# tractor_2v1.net
KiCad netlist of a schematic drawn in EAGLE
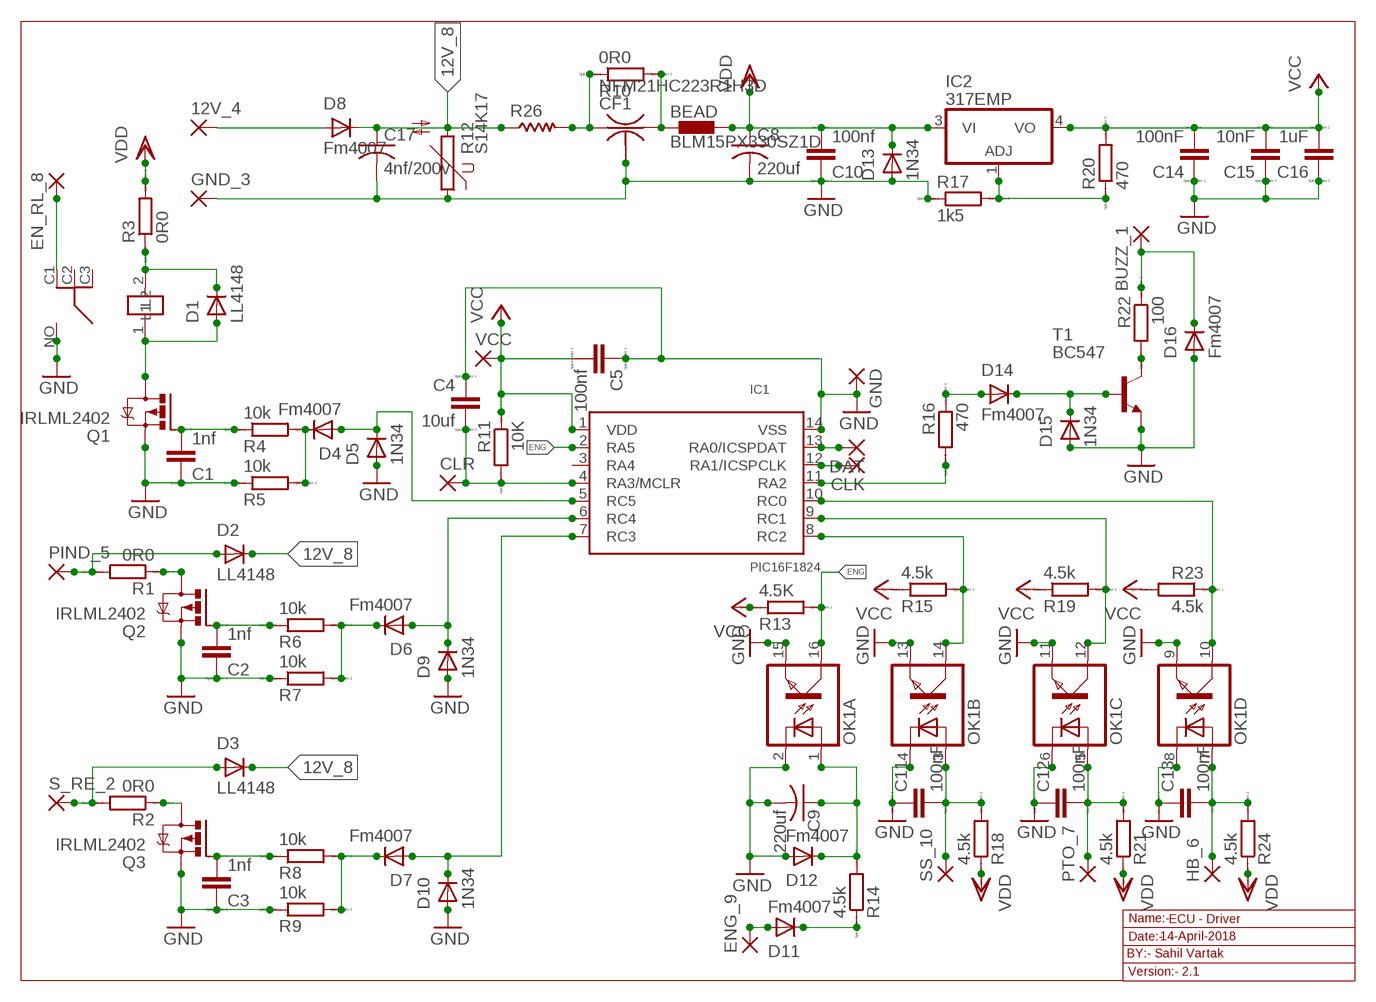
[diagram p0: schematic, sheet 1]

(export (version "E")
  (design (tool "Eeschema 10.0.6"))
  (components
    (comp (ref "12V_4")
      (value "2,54/1,1")
      (footprint "eagle-import:2,54_1,1")
      (libsource (lib "eagle-import") (part "2,54/1,1"))
    )
    (comp (ref "BEAD")
      (value "BLM15PX330SZ1D")
      (footprint "eagle-import:0402")
      (libsource (lib "eagle-import") (part "BLM15HG601SN1"))
    )
    (comp (ref "BUZZ_1")
      (value "2,54/1,1")
      (footprint "eagle-import:2,54_1,1")
      (libsource (lib "eagle-import") (part "2,54/1,1"))
    )
    (comp (ref "C1")
      (value "1nf")
      (footprint "eagle-import:C0603")
      (libsource (lib "eagle-import") (part "CC0603"))
    )
    (comp (ref "C2")
      (value "1nf")
      (footprint "eagle-import:C0603")
      (libsource (lib "eagle-import") (part "CC0603"))
    )
    (comp (ref "C3")
      (value "1nf")
      (footprint "eagle-import:C0603")
      (libsource (lib "eagle-import") (part "CC0603"))
    )
    (comp (ref "C4")
      (value "10uf")
      (footprint "eagle-import:C0603")
      (libsource (lib "eagle-import") (part "CC0603"))
    )
    (comp (ref "C5")
      (value "100nf")
      (footprint "eagle-import:C0603")
      (libsource (lib "eagle-import") (part "CC0603"))
    )
    (comp (ref "C8")
      (value "220uf")
      (footprint "eagle-import:C025-025X050")
      (libsource (lib "eagle-import") (part "C-US025-025X050"))
    )
    (comp (ref "C9")
      (value "220uf")
      (footprint "eagle-import:C025-025X050")
      (libsource (lib "eagle-import") (part "C-US025-025X050"))
    )
    (comp (ref "C10")
      (value "100nf")
      (footprint "eagle-import:C0603")
      (libsource (lib "eagle-import") (part "CC0603"))
    )
    (comp (ref "C11")
      (value "100nF")
      (footprint "eagle-import:C0603")
      (libsource (lib "eagle-import") (part "CC0603"))
    )
    (comp (ref "C12")
      (value "100nF")
      (footprint "eagle-import:C0603")
      (libsource (lib "eagle-import") (part "CC0603"))
    )
    (comp (ref "C13")
      (value "100nF")
      (footprint "eagle-import:C0603")
      (libsource (lib "eagle-import") (part "CC0603"))
    )
    (comp (ref "C14")
      (value "100nF")
      (footprint "eagle-import:C0603")
      (libsource (lib "eagle-import") (part "CC0603"))
    )
    (comp (ref "C15")
      (value "10nF")
      (footprint "eagle-import:C0603")
      (libsource (lib "eagle-import") (part "CC0603"))
    )
    (comp (ref "C16")
      (value "1uF")
      (footprint "eagle-import:C0603")
      (libsource (lib "eagle-import") (part "CC0603"))
    )
    (comp (ref "C17")
      (value "4nf/200v")
      (footprint "eagle-import:C050-045X075")
      (libsource (lib "eagle-import") (part "C-US050-045X075"))
    )
    (comp (ref "CF1")
      (value "NFM21HC223R1H3D")
      (footprint "eagle-import:NFM3DC")
      (fields (field (name "MF") "FARNELL") (field (name "MPN") "NFM3DCC470U1H3L"))
      (libsource (lib "eagle-import") (part "NFM3DC"))
    )
    (comp (ref "CLK")
      (value "1,6/0,8")
      (footprint "eagle-import:1,6_0,8")
      (libsource (lib "eagle-import") (part "1,6/0,8"))
    )
    (comp (ref "CLR")
      (value "1,6/0,8")
      (footprint "eagle-import:1,6_0,8")
      (libsource (lib "eagle-import") (part "1,6/0,8"))
    )
    (comp (ref "D1")
      (value "LL4148")
      (footprint "eagle-import:SMA-DO214AC")
      (libsource (lib "eagle-import") (part "GF1"))
    )
    (comp (ref "D2")
      (value "LL4148")
      (footprint "eagle-import:SMA-DO214AC")
      (libsource (lib "eagle-import") (part "GF1"))
    )
    (comp (ref "D3")
      (value "LL4148")
      (footprint "eagle-import:SMA-DO214AC")
      (libsource (lib "eagle-import") (part "GF1"))
    )
    (comp (ref "D4")
      (value "Fm4007")
      (footprint "eagle-import:SMA-DO214AC")
      (libsource (lib "eagle-import") (part "GF1"))
    )
    (comp (ref "D5")
      (value "1N34")
      (footprint "eagle-import:SMA-DO214AC")
      (libsource (lib "eagle-import") (part "GF1"))
    )
    (comp (ref "D6")
      (value "Fm4007")
      (footprint "eagle-import:SMA-DO214AC")
      (libsource (lib "eagle-import") (part "GF1"))
    )
    (comp (ref "D7")
      (value "Fm4007")
      (footprint "eagle-import:SMA-DO214AC")
      (libsource (lib "eagle-import") (part "GF1"))
    )
    (comp (ref "D8")
      (value "Fm4007")
      (footprint "eagle-import:SMA-DO214AC")
      (libsource (lib "eagle-import") (part "GF1"))
    )
    (comp (ref "D9")
      (value "1N34")
      (footprint "eagle-import:SMA-DO214AC")
      (libsource (lib "eagle-import") (part "GF1"))
    )
    (comp (ref "D10")
      (value "1N34")
      (footprint "eagle-import:SMA-DO214AC")
      (libsource (lib "eagle-import") (part "GF1"))
    )
    (comp (ref "D11")
      (value "Fm4007")
      (footprint "eagle-import:SMA-DO214AC")
      (libsource (lib "eagle-import") (part "GF1"))
    )
    (comp (ref "D12")
      (value "Fm4007")
      (footprint "eagle-import:SMA-DO214AC")
      (libsource (lib "eagle-import") (part "GF1"))
    )
    (comp (ref "D13")
      (value "1N34")
      (footprint "eagle-import:SMA-DO214AC")
      (libsource (lib "eagle-import") (part "GF1"))
    )
    (comp (ref "D14")
      (value "Fm4007")
      (footprint "eagle-import:SMA-DO214AC")
      (libsource (lib "eagle-import") (part "GF1"))
    )
    (comp (ref "D15")
      (value "1N34")
      (footprint "eagle-import:SMA-DO214AC")
      (libsource (lib "eagle-import") (part "GF1"))
    )
    (comp (ref "D16")
      (value "Fm4007")
      (footprint "eagle-import:SMA-DO214AC")
      (libsource (lib "eagle-import") (part "GF1"))
    )
    (comp (ref "DAT")
      (value "1,6/0,8")
      (footprint "eagle-import:1,6_0,8")
      (libsource (lib "eagle-import") (part "1,6/0,8"))
    )
    (comp (ref "ENG_9")
      (value "2,54/1,1")
      (footprint "eagle-import:2,54_1,1")
      (libsource (lib "eagle-import") (part "2,54/1,1"))
    )
    (comp (ref "EN_RL_8")
      (value "2,54/1,1")
      (footprint "eagle-import:2,54_1,1")
      (libsource (lib "eagle-import") (part "2,54/1,1"))
    )
    (comp (ref "GND")
      (value "1,6/0,8")
      (footprint "eagle-import:1,6_0,8")
      (libsource (lib "eagle-import") (part "1,6/0,8"))
    )
    (comp (ref "GND_3")
      (value "2,54/1,1")
      (footprint "eagle-import:2,54_1,1")
      (libsource (lib "eagle-import") (part "2,54/1,1"))
    )
    (comp (ref "HB_6")
      (value "2,54/1,1")
      (footprint "eagle-import:2,54_1,1")
      (libsource (lib "eagle-import") (part "2,54/1,1"))
    )
    (comp (ref "IC1")
      (value "PIC16F1824")
      (footprint "eagle-import:SO-14")
      (libsource (lib "eagle-import") (part "PIC16F1824"))
    )
    (comp (ref "IC2")
      (value "317EMP")
      (footprint "eagle-import:SOT223")
      (libsource (lib "eagle-import") (part "317EMP"))
    )
    (comp (ref "K1")
      (value "RL703")
      (footprint "eagle-import:RL703")
      (libsource (lib "eagle-import") (part "RL703"))
    )
    (comp (ref "OK1")
      (value "TLP283-4")
      (footprint "eagle-import:MINI-FLAT-16")
      (libsource (lib "eagle-import") (part "TLP283-4"))
    )
    (comp (ref "PIND_5")
      (value "2,54/1,1")
      (footprint "eagle-import:2,54_1,1")
      (libsource (lib "eagle-import") (part "2,54/1,1"))
    )
    (comp (ref "PTO_7")
      (value "2,54/1,1")
      (footprint "eagle-import:2,54_1,1")
      (libsource (lib "eagle-import") (part "2,54/1,1"))
    )
    (comp (ref "Q1")
      (value "IRLML2402")
      (footprint "eagle-import:MICRO3")
      (libsource (lib "eagle-import") (part "IRLML5203"))
    )
    (comp (ref "Q2")
      (value "IRLML2402")
      (footprint "eagle-import:MICRO3")
      (libsource (lib "eagle-import") (part "IRLML5203"))
    )
    (comp (ref "Q3")
      (value "IRLML2402")
      (footprint "eagle-import:MICRO3")
      (libsource (lib "eagle-import") (part "IRLML5203"))
    )
    (comp (ref "R1")
      (value "0R0")
      (footprint "eagle-import:R0603")
      (libsource (lib "eagle-import") (part "RR0603"))
    )
    (comp (ref "R2")
      (value "0R0")
      (footprint "eagle-import:R0603")
      (libsource (lib "eagle-import") (part "RR0603"))
    )
    (comp (ref "R3")
      (value "0R0")
      (footprint "eagle-import:R0603")
      (libsource (lib "eagle-import") (part "RR0603"))
    )
    (comp (ref "R4")
      (value "10k")
      (footprint "eagle-import:R0603")
      (libsource (lib "eagle-import") (part "RR0603"))
    )
    (comp (ref "R5")
      (value "10k")
      (footprint "eagle-import:R0603")
      (libsource (lib "eagle-import") (part "RR0603"))
    )
    (comp (ref "R6")
      (value "10k")
      (footprint "eagle-import:R0603")
      (libsource (lib "eagle-import") (part "RR0603"))
    )
    (comp (ref "R7")
      (value "10k")
      (footprint "eagle-import:R0603")
      (libsource (lib "eagle-import") (part "RR0603"))
    )
    (comp (ref "R8")
      (value "10k")
      (footprint "eagle-import:R0603")
      (libsource (lib "eagle-import") (part "RR0603"))
    )
    (comp (ref "R9")
      (value "10k")
      (footprint "eagle-import:R0603")
      (libsource (lib "eagle-import") (part "RR0603"))
    )
    (comp (ref "R10")
      (value "0R0")
      (footprint "eagle-import:R0603")
      (libsource (lib "eagle-import") (part "RR0603"))
    )
    (comp (ref "R11")
      (value "10K")
      (footprint "eagle-import:R0603")
      (libsource (lib "eagle-import") (part "RR0603"))
    )
    (comp (ref "R12")
      (value "S14K17")
      (footprint "eagle-import:S14K17")
      (libsource (lib "eagle-import") (part "S14K17"))
    )
    (comp (ref "R13")
      (value "4.5K")
      (footprint "eagle-import:R0603")
      (libsource (lib "eagle-import") (part "RR0603"))
    )
    (comp (ref "R14")
      (value "4.5k")
      (footprint "eagle-import:R0603")
      (libsource (lib "eagle-import") (part "RR0603"))
    )
    (comp (ref "R15")
      (value "4.5k")
      (footprint "eagle-import:R0603")
      (libsource (lib "eagle-import") (part "RR0603"))
    )
    (comp (ref "R16")
      (value "470")
      (footprint "eagle-import:R0603")
      (libsource (lib "eagle-import") (part "RR0603"))
    )
    (comp (ref "R17")
      (value "1k5")
      (footprint "eagle-import:R0603")
      (libsource (lib "eagle-import") (part "RR0603"))
    )
    (comp (ref "R18")
      (value "4.5k")
      (footprint "eagle-import:R0603")
      (libsource (lib "eagle-import") (part "RR0603"))
    )
    (comp (ref "R19")
      (value "4.5k")
      (footprint "eagle-import:R0603")
      (libsource (lib "eagle-import") (part "RR0603"))
    )
    (comp (ref "R20")
      (value "470")
      (footprint "eagle-import:R0603")
      (libsource (lib "eagle-import") (part "RR0603"))
    )
    (comp (ref "R21")
      (value "4.5k")
      (footprint "eagle-import:R0603")
      (libsource (lib "eagle-import") (part "RR0603"))
    )
    (comp (ref "R22")
      (value "100")
      (footprint "eagle-import:R0603")
      (libsource (lib "eagle-import") (part "RR0603"))
    )
    (comp (ref "R23")
      (value "4.5k")
      (footprint "eagle-import:R0603")
      (libsource (lib "eagle-import") (part "RR0603"))
    )
    (comp (ref "R24")
      (value "4.5k")
      (footprint "eagle-import:R0603")
      (libsource (lib "eagle-import") (part "RR0603"))
    )
    (comp (ref "R26")
      (value "R-US_WSC2515")
      (footprint "eagle-import:WSC2515")
      (libsource (lib "eagle-import") (part "R-US_WSC2515"))
    )
    (comp (ref "SS_10")
      (value "2,54/1,1")
      (footprint "eagle-import:2,54_1,1")
      (libsource (lib "eagle-import") (part "2,54/1,1"))
    )
    (comp (ref "S_RE_2")
      (value "2,54/1,1")
      (footprint "eagle-import:2,54_1,1")
      (libsource (lib "eagle-import") (part "2,54/1,1"))
    )
    (comp (ref "T1")
      (value "BC547")
      (footprint "eagle-import:TO92")
      (libsource (lib "eagle-import") (part "BC547"))
    )
    (comp (ref "VCC")
      (value "1,6/0,8")
      (footprint "eagle-import:1,6_0,8")
      (libsource (lib "eagle-import") (part "1,6/0,8"))
    )
  )
  (nets
    (net (code "1") (name "12V_8") (class "Default")
      (node (ref "C17") (pin "1") (pinfunction "1_1") (pintype "passive"))
      (node (ref "D2") (pin "K") (pinfunction "C_K") (pintype "passive"))
      (node (ref "D3") (pin "K") (pinfunction "C_K") (pintype "passive"))
      (node (ref "D8") (pin "K") (pinfunction "C_K") (pintype "passive"))
      (node (ref "R12") (pin "2") (pinfunction "2_2") (pintype "passive"))
      (node (ref "R26") (pin "1") (pinfunction "1_1") (pintype "passive"))
    )
    (net (code "2") (name "ENG") (class "Default")
      (node (ref "IC1") (pin "2") (pinfunction "RA5_2") (pintype "bidirectional"))
      (node (ref "OK1") (pin "16") (pinfunction "COL_16") (pintype "passive"))
      (node (ref "R13") (pin "2") (pinfunction "2_2") (pintype "passive"))
    )
    (net (code "3") (name "GND") (class "Default")
      (node (ref "C1") (pin "1") (pinfunction "1_1") (pintype "passive"))
      (node (ref "C10") (pin "1") (pinfunction "1_1") (pintype "passive"))
      (node (ref "C11") (pin "1") (pinfunction "1_1") (pintype "passive"))
      (node (ref "C12") (pin "1") (pinfunction "1_1") (pintype "passive"))
      (node (ref "C13") (pin "1") (pinfunction "1_1") (pintype "passive"))
      (node (ref "C14") (pin "1") (pinfunction "1_1") (pintype "passive"))
      (node (ref "C15") (pin "1") (pinfunction "1_1") (pintype "passive"))
      (node (ref "C16") (pin "1") (pinfunction "1_1") (pintype "passive"))
      (node (ref "C17") (pin "2") (pinfunction "2_2") (pintype "passive"))
      (node (ref "C2") (pin "1") (pinfunction "1_1") (pintype "passive"))
      (node (ref "C3") (pin "1") (pinfunction "1_1") (pintype "passive"))
      (node (ref "C4") (pin "1") (pinfunction "1_1") (pintype "passive"))
      (node (ref "C5") (pin "1") (pinfunction "1_1") (pintype "passive"))
      (node (ref "C8") (pin "2") (pinfunction "2_2") (pintype "passive"))
      (node (ref "C9") (pin "2") (pinfunction "2_2") (pintype "passive"))
      (node (ref "CF1") (pin "2@1") (pinfunction "2_2@1") (pintype "passive"))
      (node (ref "D10") (pin "A") (pinfunction "A_A") (pintype "passive"))
      (node (ref "D12") (pin "A") (pinfunction "A_A") (pintype "passive"))
      (node (ref "D13") (pin "A") (pinfunction "A_A") (pintype "passive"))
      (node (ref "D15") (pin "A") (pinfunction "A_A") (pintype "passive"))
      (node (ref "D16") (pin "A") (pinfunction "A_A") (pintype "passive"))
      (node (ref "D5") (pin "A") (pinfunction "A_A") (pintype "passive"))
      (node (ref "D9") (pin "A") (pinfunction "A_A") (pintype "passive"))
      (node (ref "GND") (pin "1") (pinfunction "P_1") (pintype "passive"))
      (node (ref "GND_3") (pin "1") (pinfunction "P_1") (pintype "passive"))
      (node (ref "IC1") (pin "14") (pinfunction "VSS_14") (pintype "bidirectional"))
      (node (ref "K1") (pin "NO") (pinfunction "NO_NO") (pintype "bidirectional"))
      (node (ref "OK1") (pin "11") (pinfunction "EMIT_11") (pintype "passive"))
      (node (ref "OK1") (pin "13") (pinfunction "EMIT_13") (pintype "passive"))
      (node (ref "OK1") (pin "15") (pinfunction "EMIT_15") (pintype "passive"))
      (node (ref "OK1") (pin "2") (pinfunction "C_2") (pintype "passive"))
      (node (ref "OK1") (pin "4") (pinfunction "C_4") (pintype "passive"))
      (node (ref "OK1") (pin "6") (pinfunction "C_6") (pintype "passive"))
      (node (ref "OK1") (pin "8") (pinfunction "C_8") (pintype "passive"))
      (node (ref "OK1") (pin "9") (pinfunction "EMIT_9") (pintype "passive"))
      (node (ref "Q1") (pin "2") (pinfunction "S_2") (pintype "passive"))
      (node (ref "Q2") (pin "2") (pinfunction "S_2") (pintype "passive"))
      (node (ref "Q3") (pin "2") (pinfunction "S_2") (pintype "passive"))
      (node (ref "R12") (pin "1") (pinfunction "1_1") (pintype "passive"))
      (node (ref "R17") (pin "1") (pinfunction "1_1") (pintype "passive"))
      (node (ref "R5") (pin "1") (pinfunction "1_1") (pintype "passive"))
      (node (ref "R7") (pin "1") (pinfunction "1_1") (pintype "passive"))
      (node (ref "R9") (pin "1") (pinfunction "1_1") (pintype "passive"))
      (node (ref "T1") (pin "1") (pinfunction "E_1") (pintype "passive"))
    )
    (net (code "4") (name "Net-(12V_4-P)") (class "Default")
      (node (ref "12V_4") (pin "1") (pinfunction "P_1") (pintype "passive"))
      (node (ref "D8") (pin "A") (pinfunction "A_A") (pintype "passive"))
    )
    (net (code "5") (name "Net-(BEAD-Pad1)") (class "Default")
      (node (ref "BEAD") (pin "1") (pinfunction "1_1") (pintype "passive"))
      (node (ref "CF1") (pin "3") (pinfunction "3_3") (pintype "passive"))
      (node (ref "R10") (pin "2") (pinfunction "2_2") (pintype "passive"))
    )
    (net (code "6") (name "Net-(BUZZ_1-P)") (class "Default")
      (node (ref "BUZZ_1") (pin "1") (pinfunction "P_1") (pintype "passive"))
      (node (ref "D16") (pin "K") (pinfunction "C_K") (pintype "passive"))
      (node (ref "R22") (pin "1") (pinfunction "1_1") (pintype "passive"))
    )
    (net (code "7") (name "Net-(CF1-Pad1)") (class "Default")
      (node (ref "CF1") (pin "1") (pinfunction "1_1") (pintype "passive"))
      (node (ref "R10") (pin "1") (pinfunction "1_1") (pintype "passive"))
      (node (ref "R26") (pin "2") (pinfunction "2_2") (pintype "passive"))
    )
    (net (code "8") (name "Net-(CLK-P)") (class "Default")
      (node (ref "CLK") (pin "1") (pinfunction "P_1") (pintype "passive"))
      (node (ref "IC1") (pin "12") (pinfunction "RA1/ICSPCLK_12") (pintype "bidirectional"))
    )
    (net (code "9") (name "Net-(CLR-P)") (class "Default")
      (node (ref "C4") (pin "2") (pinfunction "2_2") (pintype "passive"))
      (node (ref "CLR") (pin "1") (pinfunction "P_1") (pintype "passive"))
      (node (ref "IC1") (pin "4") (pinfunction "RA3/MCLR_4") (pintype "bidirectional"))
      (node (ref "R11") (pin "2") (pinfunction "2_2") (pintype "passive"))
    )
    (net (code "10") (name "Net-(D1-C)") (class "Default")
      (node (ref "D1") (pin "K") (pinfunction "C_K") (pintype "passive"))
      (node (ref "K1") (pin "2") (pinfunction "L1_2") (pintype "bidirectional"))
      (node (ref "R3") (pin "1") (pinfunction "1_1") (pintype "passive"))
    )
    (net (code "11") (name "Net-(D4-C)") (class "Default")
      (node (ref "D4") (pin "K") (pinfunction "C_K") (pintype "passive"))
      (node (ref "R4") (pin "2") (pinfunction "2_2") (pintype "passive"))
      (node (ref "R5") (pin "2") (pinfunction "2_2") (pintype "passive"))
    )
    (net (code "12") (name "Net-(D5-C)") (class "Default")
      (node (ref "D4") (pin "A") (pinfunction "A_A") (pintype "passive"))
      (node (ref "D5") (pin "K") (pinfunction "C_K") (pintype "passive"))
      (node (ref "IC1") (pin "5") (pinfunction "RC5_5") (pintype "bidirectional"))
    )
    (net (code "13") (name "Net-(D6-C)") (class "Default")
      (node (ref "D6") (pin "K") (pinfunction "C_K") (pintype "passive"))
      (node (ref "R6") (pin "2") (pinfunction "2_2") (pintype "passive"))
      (node (ref "R7") (pin "2") (pinfunction "2_2") (pintype "passive"))
    )
    (net (code "14") (name "Net-(D7-C)") (class "Default")
      (node (ref "D7") (pin "K") (pinfunction "C_K") (pintype "passive"))
      (node (ref "R8") (pin "2") (pinfunction "2_2") (pintype "passive"))
      (node (ref "R9") (pin "2") (pinfunction "2_2") (pintype "passive"))
    )
    (net (code "15") (name "Net-(D9-C)") (class "Default")
      (node (ref "D6") (pin "A") (pinfunction "A_A") (pintype "passive"))
      (node (ref "D9") (pin "K") (pinfunction "C_K") (pintype "passive"))
      (node (ref "IC1") (pin "6") (pinfunction "RC4_6") (pintype "bidirectional"))
    )
    (net (code "16") (name "Net-(D10-C)") (class "Default")
      (node (ref "D10") (pin "K") (pinfunction "C_K") (pintype "passive"))
      (node (ref "D7") (pin "A") (pinfunction "A_A") (pintype "passive"))
      (node (ref "IC1") (pin "7") (pinfunction "RC3_7") (pintype "bidirectional"))
    )
    (net (code "17") (name "Net-(D11-C)") (class "Default")
      (node (ref "D11") (pin "K") (pinfunction "C_K") (pintype "passive"))
      (node (ref "R14") (pin "1") (pinfunction "1_1") (pintype "passive"))
    )
    (net (code "18") (name "Net-(D12-C)") (class "Default")
      (node (ref "C9") (pin "1") (pinfunction "1_1") (pintype "passive"))
      (node (ref "D12") (pin "K") (pinfunction "C_K") (pintype "passive"))
      (node (ref "OK1") (pin "1") (pinfunction "A_1") (pintype "passive"))
      (node (ref "R14") (pin "2") (pinfunction "2_2") (pintype "passive"))
    )
    (net (code "19") (name "Net-(D14-C)") (class "Default")
      (node (ref "D14") (pin "K") (pinfunction "C_K") (pintype "passive"))
      (node (ref "D15") (pin "K") (pinfunction "C_K") (pintype "passive"))
      (node (ref "T1") (pin "2") (pinfunction "B_2") (pintype "passive"))
    )
    (net (code "20") (name "Net-(D14-PadA)") (class "Default")
      (node (ref "D14") (pin "A") (pinfunction "A_A") (pintype "passive"))
      (node (ref "R16") (pin "1") (pinfunction "1_1") (pintype "passive"))
    )
    (net (code "21") (name "Net-(DAT-P)") (class "Default")
      (node (ref "DAT") (pin "1") (pinfunction "P_1") (pintype "passive"))
      (node (ref "IC1") (pin "13") (pinfunction "RA0/ICSPDAT_13") (pintype "bidirectional"))
    )
    (net (code "22") (name "Net-(ENG_9-P)") (class "Default")
      (node (ref "D11") (pin "A") (pinfunction "A_A") (pintype "passive"))
      (node (ref "ENG_9") (pin "1") (pinfunction "P_1") (pintype "passive"))
    )
    (net (code "23") (name "Net-(EN_RL_8-P)") (class "Default")
      (node (ref "EN_RL_8") (pin "1") (pinfunction "P_1") (pintype "passive"))
      (node (ref "K1") (pin "C1") (pinfunction "C1_C1") (pintype "bidirectional"))
    )
    (net (code "24") (name "Net-(HB_6-P)") (class "Default")
      (node (ref "C13") (pin "2") (pinfunction "2_2") (pintype "passive"))
      (node (ref "HB_6") (pin "1") (pinfunction "P_1") (pintype "passive"))
      (node (ref "OK1") (pin "7") (pinfunction "A_7") (pintype "passive"))
      (node (ref "R24") (pin "2") (pinfunction "2_2") (pintype "passive"))
    )
    (net (code "25") (name "Net-(IC1-RA2)") (class "Default")
      (node (ref "IC1") (pin "11") (pinfunction "RA2_11") (pintype "bidirectional"))
      (node (ref "R16") (pin "2") (pinfunction "2_2") (pintype "passive"))
    )
    (net (code "26") (name "Net-(IC1-RC0)") (class "Default")
      (node (ref "IC1") (pin "10") (pinfunction "RC0_10") (pintype "bidirectional"))
      (node (ref "OK1") (pin "10") (pinfunction "COL_10") (pintype "passive"))
      (node (ref "R23") (pin "1") (pinfunction "1_1") (pintype "passive"))
    )
    (net (code "27") (name "Net-(IC1-RC1)") (class "Default")
      (node (ref "IC1") (pin "9") (pinfunction "RC1_9") (pintype "bidirectional"))
      (node (ref "OK1") (pin "12") (pinfunction "COL_12") (pintype "passive"))
      (node (ref "R19") (pin "2") (pinfunction "2_2") (pintype "passive"))
    )
    (net (code "28") (name "Net-(IC1-RC2)") (class "Default")
      (node (ref "IC1") (pin "8") (pinfunction "RC2_8") (pintype "bidirectional"))
      (node (ref "OK1") (pin "14") (pinfunction "COL_14") (pintype "passive"))
      (node (ref "R15") (pin "2") (pinfunction "2_2") (pintype "passive"))
    )
    (net (code "29") (name "Net-(IC2-ADJ)") (class "Default")
      (node (ref "IC2") (pin "1") (pinfunction "ADJ_1") (pintype "input"))
      (node (ref "R17") (pin "2") (pinfunction "2_2") (pintype "passive"))
      (node (ref "R20") (pin "1") (pinfunction "1_1") (pintype "passive"))
    )
    (net (code "30") (name "Net-(K1-L2)") (class "Default")
      (node (ref "D1") (pin "A") (pinfunction "A_A") (pintype "passive"))
      (node (ref "K1") (pin "1") (pinfunction "L2_1") (pintype "bidirectional"))
      (node (ref "Q1") (pin "3") (pinfunction "D_3") (pintype "passive"))
    )
    (net (code "31") (name "Net-(OK1B-A)") (class "Default")
      (node (ref "C11") (pin "2") (pinfunction "2_2") (pintype "passive"))
      (node (ref "OK1") (pin "3") (pinfunction "A_3") (pintype "passive"))
      (node (ref "R18") (pin "2") (pinfunction "2_2") (pintype "passive"))
      (node (ref "SS_10") (pin "1") (pinfunction "P_1") (pintype "passive"))
    )
    (net (code "32") (name "Net-(OK1C-A)") (class "Default")
      (node (ref "C12") (pin "2") (pinfunction "2_2") (pintype "passive"))
      (node (ref "OK1") (pin "5") (pinfunction "A_5") (pintype "passive"))
      (node (ref "PTO_7") (pin "1") (pinfunction "P_1") (pintype "passive"))
      (node (ref "R21") (pin "2") (pinfunction "2_2") (pintype "passive"))
    )
    (net (code "33") (name "Net-(PIND_5-P)") (class "Default")
      (node (ref "D2") (pin "A") (pinfunction "A_A") (pintype "passive"))
      (node (ref "PIND_5") (pin "1") (pinfunction "P_1") (pintype "passive"))
      (node (ref "R1") (pin "2") (pinfunction "2_2") (pintype "passive"))
    )
    (net (code "34") (name "Net-(Q1-G)") (class "Default")
      (node (ref "C1") (pin "2") (pinfunction "2_2") (pintype "passive"))
      (node (ref "Q1") (pin "1") (pinfunction "G_1") (pintype "passive"))
      (node (ref "R4") (pin "1") (pinfunction "1_1") (pintype "passive"))
    )
    (net (code "35") (name "Net-(Q2-D)") (class "Default")
      (node (ref "Q2") (pin "3") (pinfunction "D_3") (pintype "passive"))
      (node (ref "R1") (pin "1") (pinfunction "1_1") (pintype "passive"))
    )
    (net (code "36") (name "Net-(Q2-G)") (class "Default")
      (node (ref "C2") (pin "2") (pinfunction "2_2") (pintype "passive"))
      (node (ref "Q2") (pin "1") (pinfunction "G_1") (pintype "passive"))
      (node (ref "R6") (pin "1") (pinfunction "1_1") (pintype "passive"))
    )
    (net (code "37") (name "Net-(Q3-D)") (class "Default")
      (node (ref "Q3") (pin "3") (pinfunction "D_3") (pintype "passive"))
      (node (ref "R2") (pin "1") (pinfunction "1_1") (pintype "passive"))
    )
    (net (code "38") (name "Net-(Q3-G)") (class "Default")
      (node (ref "C3") (pin "2") (pinfunction "2_2") (pintype "passive"))
      (node (ref "Q3") (pin "1") (pinfunction "G_1") (pintype "passive"))
      (node (ref "R8") (pin "1") (pinfunction "1_1") (pintype "passive"))
    )
    (net (code "39") (name "Net-(S_RE_2-P)") (class "Default")
      (node (ref "D3") (pin "A") (pinfunction "A_A") (pintype "passive"))
      (node (ref "R2") (pin "2") (pinfunction "2_2") (pintype "passive"))
      (node (ref "S_RE_2") (pin "1") (pinfunction "P_1") (pintype "passive"))
    )
    (net (code "40") (name "Net-(T1-C)") (class "Default")
      (node (ref "R22") (pin "2") (pinfunction "2_2") (pintype "passive"))
      (node (ref "T1") (pin "3") (pinfunction "C_3") (pintype "passive"))
    )
    (net (code "41") (name "VCC") (class "Default")
      (node (ref "C14") (pin "2") (pinfunction "2_2") (pintype "passive"))
      (node (ref "C15") (pin "2") (pinfunction "2_2") (pintype "passive"))
      (node (ref "C16") (pin "2") (pinfunction "2_2") (pintype "passive"))
      (node (ref "C5") (pin "2") (pinfunction "2_2") (pintype "passive"))
      (node (ref "IC1") (pin "1") (pinfunction "VDD_1") (pintype "bidirectional"))
      (node (ref "IC2") (pin "4") (pinfunction "VO_4") (pintype "passive"))
      (node (ref "R11") (pin "1") (pinfunction "1_1") (pintype "passive"))
      (node (ref "R13") (pin "1") (pinfunction "1_1") (pintype "passive"))
      (node (ref "R15") (pin "1") (pinfunction "1_1") (pintype "passive"))
      (node (ref "R19") (pin "1") (pinfunction "1_1") (pintype "passive"))
      (node (ref "R20") (pin "2") (pinfunction "2_2") (pintype "passive"))
      (node (ref "R23") (pin "2") (pinfunction "2_2") (pintype "passive"))
      (node (ref "VCC") (pin "1") (pinfunction "P_1") (pintype "passive"))
    )
    (net (code "42") (name "VDD") (class "Default")
      (node (ref "BEAD") (pin "2") (pinfunction "2_2") (pintype "passive"))
      (node (ref "C10") (pin "2") (pinfunction "2_2") (pintype "passive"))
      (node (ref "C8") (pin "1") (pinfunction "1_1") (pintype "passive"))
      (node (ref "D13") (pin "K") (pinfunction "C_K") (pintype "passive"))
      (node (ref "IC2") (pin "3") (pinfunction "VI_3") (pintype "input"))
      (node (ref "R18") (pin "1") (pinfunction "1_1") (pintype "passive"))
      (node (ref "R21") (pin "1") (pinfunction "1_1") (pintype "passive"))
      (node (ref "R24") (pin "1") (pinfunction "1_1") (pintype "passive"))
      (node (ref "R3") (pin "2") (pinfunction "2_2") (pintype "passive"))
    )
    (net (code "43") (name "unconnected-(CF1-2-Pad2@2)") (class "Default")
      (node (ref "CF1") (pin "2@2") (pinfunction "2_2@2") (pintype "passive"))
    )
    (net (code "44") (name "unconnected-(IC1-RA4-Pad3)") (class "Default")
      (node (ref "IC1") (pin "3") (pinfunction "RA4_3") (pintype "bidirectional"))
    )
    (net (code "45") (name "unconnected-(K1-PadC2)") (class "Default")
      (node (ref "K1") (pin "C2") (pinfunction "C2_C2") (pintype "bidirectional"))
    )
    (net (code "46") (name "unconnected-(K1-PadC3)") (class "Default")
      (node (ref "K1") (pin "C3") (pinfunction "C3_C3") (pintype "bidirectional"))
    )
  )
)
